# Main.net
KiCad netlist of a schematic drawn in Altium Designer
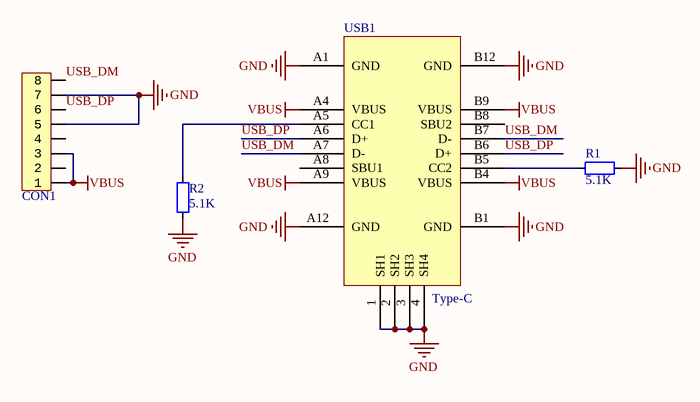
[diagram p0: Main.SchDoc]

(export (version "E")
  (design (tool "Eeschema 10.0.6"))
  (components
    (comp (ref "CON1")
      (value "FFC_0.5_8")
      (footprint "FFC_0.5_8")
      (description "FFC")
      (libsource (lib "KitSprout") (part "FFC_0.5_8"))
    )
    (comp (ref "R1")
      (value "5.1K")
      (footprint "RES_0402")
      (description "Resistor")
      (libsource (lib "") (part "电阻-0402_1"))
    )
    (comp (ref "R2")
      (value "5.1K")
      (footprint "RES_0402")
      (description "Resistor")
      (libsource (lib "MyPcbLib") (part "电阻-0402"))
    )
    (comp (ref "USB1")
      (value "Type-C")
      (footprint "Type-C-TOP")
      (libsource (lib "MyPcbLib") (part "USB-Type-C-TOP"))
    )
  )
  (nets
    (net (code "1") (name "/USB_DM") (class "Default")
      (node (ref "CON1") (pin "8") (pinfunction "8_8") (pintype "passive"))
      (node (ref "USB1") (pin "A7") (pinfunction "D-_A7") (pintype "passive"))
      (node (ref "USB1") (pin "B7") (pinfunction "D-_B7") (pintype "passive"))
    )
    (net (code "2") (name "/USB_DP") (class "Default")
      (node (ref "CON1") (pin "6") (pinfunction "6_6") (pintype "passive"))
      (node (ref "USB1") (pin "A6") (pinfunction "D+_A6") (pintype "passive"))
      (node (ref "USB1") (pin "B6") (pinfunction "D+_B6") (pintype "passive"))
    )
    (net (code "3") (name "GND") (class "Default")
      (node (ref "CON1") (pin "5") (pinfunction "5_5") (pintype "passive"))
      (node (ref "CON1") (pin "7") (pinfunction "7_7") (pintype "passive"))
      (node (ref "R1") (pin "1") (pinfunction "1_1") (pintype "passive"))
      (node (ref "R2") (pin "2") (pinfunction "2_2") (pintype "passive"))
      (node (ref "USB1") (pin "1") (pinfunction "SH1_1") (pintype "passive"))
      (node (ref "USB1") (pin "2") (pinfunction "SH2_2") (pintype "passive"))
      (node (ref "USB1") (pin "3") (pinfunction "SH3_3") (pintype "passive"))
      (node (ref "USB1") (pin "4") (pinfunction "SH4_4") (pintype "passive"))
      (node (ref "USB1") (pin "A1") (pinfunction "GND_A1") (pintype "passive"))
      (node (ref "USB1") (pin "A12") (pinfunction "GND_A12") (pintype "passive"))
      (node (ref "USB1") (pin "B1") (pinfunction "GND_B1") (pintype "passive"))
      (node (ref "USB1") (pin "B12") (pinfunction "GND_B12") (pintype "passive"))
    )
    (net (code "4") (name "Net-(USB1-CC1)") (class "Default")
      (node (ref "R2") (pin "1") (pinfunction "1_1") (pintype "passive"))
      (node (ref "USB1") (pin "A5") (pinfunction "CC1_A5") (pintype "passive"))
    )
    (net (code "5") (name "Net-(USB1-CC2)") (class "Default")
      (node (ref "R1") (pin "2") (pinfunction "2_2") (pintype "passive"))
      (node (ref "USB1") (pin "B5") (pinfunction "CC2_B5") (pintype "passive"))
    )
    (net (code "6") (name "VBUS") (class "Default")
      (node (ref "CON1") (pin "1") (pinfunction "1_1") (pintype "passive"))
      (node (ref "CON1") (pin "3") (pinfunction "3_3") (pintype "passive"))
      (node (ref "USB1") (pin "A4") (pinfunction "VBUS_A4") (pintype "passive"))
      (node (ref "USB1") (pin "A9") (pinfunction "VBUS_A9") (pintype "passive"))
      (node (ref "USB1") (pin "B4") (pinfunction "VBUS_B4") (pintype "passive"))
      (node (ref "USB1") (pin "B9") (pinfunction "VBUS_B9") (pintype "passive"))
    )
    (net (code "7") (name "unconnected-(CON1-Pad2)") (class "Default")
      (node (ref "CON1") (pin "2") (pinfunction "2_2") (pintype "passive"))
    )
    (net (code "8") (name "unconnected-(CON1-Pad4)") (class "Default")
      (node (ref "CON1") (pin "4") (pinfunction "4_4") (pintype "passive"))
    )
    (net (code "9") (name "unconnected-(USB1-SBU1-PadA8)") (class "Default")
      (node (ref "USB1") (pin "A8") (pinfunction "SBU1_A8") (pintype "passive"))
    )
    (net (code "10") (name "unconnected-(USB1-SBU2-PadB8)") (class "Default")
      (node (ref "USB1") (pin "B8") (pinfunction "SBU2_B8") (pintype "passive"))
    )
  )
)
